# Brushless_Slave2.net
KiCad netlist of a schematic drawn in EAGLE
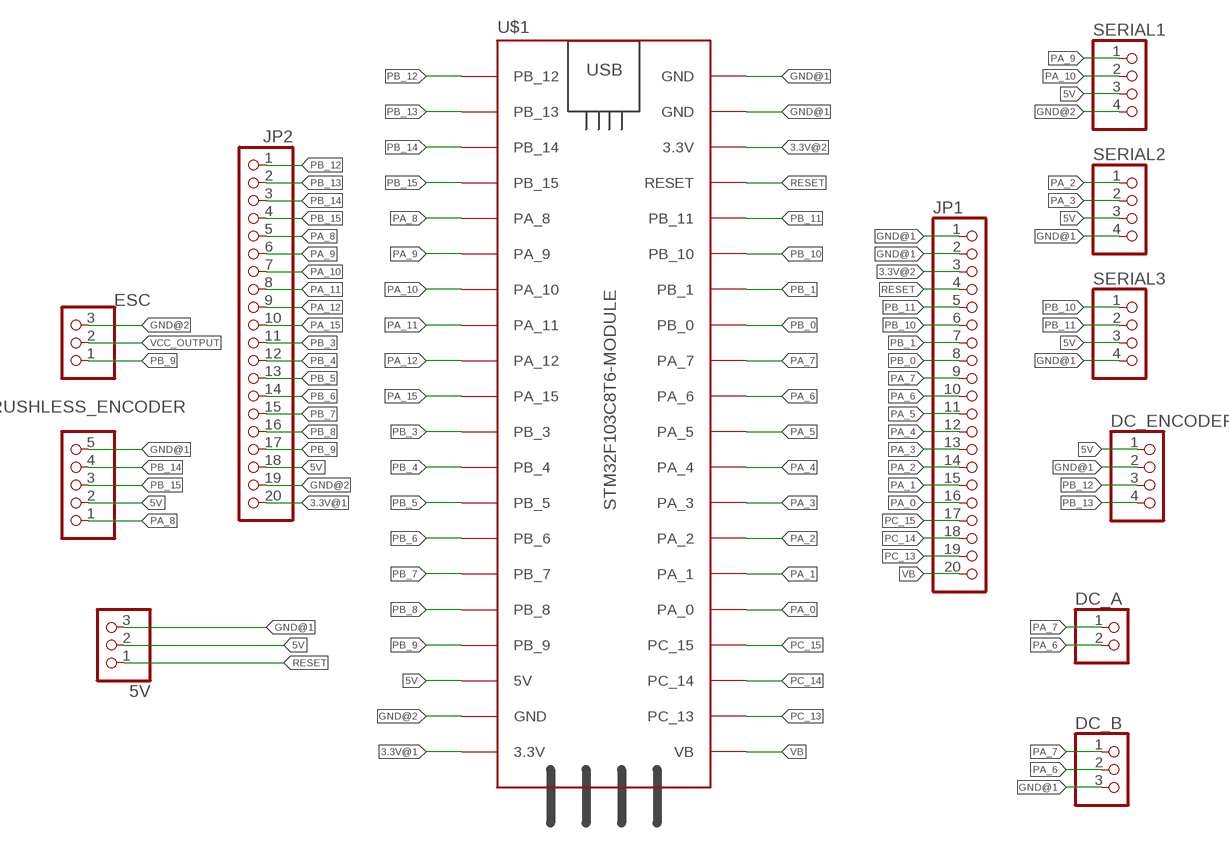
[diagram p0: schematic, sheet 1]

(export (version "E")
  (design (tool "Eeschema 10.0.6"))
  (components
    (comp (ref "5V")
      (value "PINHD-3_DATA")
      (footprint "eagle-import:1X03_DATA")
      (libsource (lib "eagle-import") (part "PINHD-3_DATA"))
    )
    (comp (ref "BRUSHLESS_ENCODER")
      (value "PINHD-5_DATA")
      (footprint "eagle-import:1X05_DATA")
      (libsource (lib "eagle-import") (part "PINHD-5_DATA"))
    )
    (comp (ref "DC_A")
      (value "PINHD-2_DATA")
      (footprint "eagle-import:1X02_DATA")
      (libsource (lib "eagle-import") (part "PINHD-2_DATA"))
    )
    (comp (ref "DC_B")
      (value "PINHD-3_DATA")
      (footprint "eagle-import:1X03_DATA")
      (libsource (lib "eagle-import") (part "PINHD-3_DATA"))
    )
    (comp (ref "DC_ENCODER")
      (value "PINHD-4_DATA")
      (footprint "eagle-import:1X04_DATA")
      (libsource (lib "eagle-import") (part "PINHD-4_DATA"))
    )
    (comp (ref "ESC")
      (value "PINHD-3_DATA")
      (footprint "eagle-import:1X03_DATA")
      (libsource (lib "eagle-import") (part "PINHD-3_DATA"))
    )
    (comp (ref "JP1")
      (value "PINHD-1X20")
      (footprint "eagle-import:1X20")
      (libsource (lib "eagle-import") (part "PINHD-1X20"))
    )
    (comp (ref "JP2")
      (value "PINHD-1X20")
      (footprint "eagle-import:1X20")
      (libsource (lib "eagle-import") (part "PINHD-1X20"))
    )
    (comp (ref "SERIAL1")
      (value "PINHD-4_DATA")
      (footprint "eagle-import:1X04_DATA")
      (libsource (lib "eagle-import") (part "PINHD-4_DATA"))
    )
    (comp (ref "SERIAL2")
      (value "PINHD-4_DATA")
      (footprint "eagle-import:1X04_DATA")
      (libsource (lib "eagle-import") (part "PINHD-4_DATA"))
    )
    (comp (ref "SERIAL3")
      (value "PINHD-4_DATA")
      (footprint "eagle-import:1X04_DATA")
      (libsource (lib "eagle-import") (part "PINHD-4_DATA"))
    )
    (comp (ref "U$1")
      (value "STM32F103C8T6-MODULE")
      (footprint "eagle-import:STM32F103C8T6-MODULE")
      (libsource (lib "eagle-import") (part "STM32F103C8T6-MODULE"))
    )
  )
  (nets
    (net (code "1") (name "3.3V@1") (class "Default")
      (node (ref "JP2") (pin "20") (pinfunction "20_20") (pintype "passive"))
      (node (ref "U$1") (pin "3.3V_1") (pinfunction "3.3V_3.3V_1") (pintype "bidirectional"))
    )
    (net (code "2") (name "3.3V@2") (class "Default")
      (node (ref "JP1") (pin "3") (pinfunction "3_3") (pintype "passive"))
      (node (ref "U$1") (pin "3.3V_2") (pinfunction "3.3V_3.3V_2") (pintype "bidirectional"))
    )
    (net (code "3") (name "5V") (class "Default")
      (node (ref "5V") (pin "2") (pinfunction "2_2") (pintype "passive"))
      (node (ref "BRUSHLESS_ENCODER") (pin "2") (pinfunction "2_2") (pintype "passive"))
      (node (ref "DC_ENCODER") (pin "1") (pinfunction "1_1") (pintype "passive"))
      (node (ref "JP2") (pin "18") (pinfunction "18_18") (pintype "passive"))
      (node (ref "SERIAL1") (pin "3") (pinfunction "3_3") (pintype "passive"))
      (node (ref "SERIAL2") (pin "3") (pinfunction "3_3") (pintype "passive"))
      (node (ref "SERIAL3") (pin "3") (pinfunction "3_3") (pintype "passive"))
      (node (ref "U$1") (pin "5V") (pinfunction "5V_5V") (pintype "bidirectional"))
    )
    (net (code "4") (name "GND@1") (class "Default")
      (node (ref "5V") (pin "3") (pinfunction "3_3") (pintype "passive"))
      (node (ref "BRUSHLESS_ENCODER") (pin "5") (pinfunction "5_5") (pintype "passive"))
      (node (ref "DC_B") (pin "3") (pinfunction "3_3") (pintype "passive"))
      (node (ref "DC_ENCODER") (pin "2") (pinfunction "2_2") (pintype "passive"))
      (node (ref "JP1") (pin "1") (pinfunction "1_1") (pintype "passive"))
      (node (ref "JP1") (pin "2") (pinfunction "2_2") (pintype "passive"))
      (node (ref "SERIAL2") (pin "4") (pinfunction "4_4") (pintype "passive"))
      (node (ref "SERIAL3") (pin "4") (pinfunction "4_4") (pintype "passive"))
      (node (ref "U$1") (pin "GND_2") (pinfunction "GND_GND_2") (pintype "bidirectional"))
      (node (ref "U$1") (pin "GND_3") (pinfunction "GND_GND_3") (pintype "power_in"))
    )
    (net (code "5") (name "GND@2") (class "Default")
      (node (ref "ESC") (pin "3") (pinfunction "3_3") (pintype "passive"))
      (node (ref "JP2") (pin "19") (pinfunction "19_19") (pintype "passive"))
      (node (ref "SERIAL1") (pin "4") (pinfunction "4_4") (pintype "passive"))
      (node (ref "U$1") (pin "GND_1") (pinfunction "GND_GND_1") (pintype "bidirectional"))
    )
    (net (code "6") (name "PA_0") (class "Default")
      (node (ref "JP1") (pin "16") (pinfunction "16_16") (pintype "passive"))
      (node (ref "U$1") (pin "PA_0") (pinfunction "PA_0_PA_0") (pintype "bidirectional"))
    )
    (net (code "7") (name "PA_1") (class "Default")
      (node (ref "JP1") (pin "15") (pinfunction "15_15") (pintype "passive"))
      (node (ref "U$1") (pin "PA_1") (pinfunction "PA_1_PA_1") (pintype "bidirectional"))
    )
    (net (code "8") (name "PA_2") (class "Default")
      (node (ref "JP1") (pin "14") (pinfunction "14_14") (pintype "passive"))
      (node (ref "SERIAL2") (pin "1") (pinfunction "1_1") (pintype "passive"))
      (node (ref "U$1") (pin "PA_2") (pinfunction "PA_2_PA_2") (pintype "bidirectional"))
    )
    (net (code "9") (name "PA_3") (class "Default")
      (node (ref "JP1") (pin "13") (pinfunction "13_13") (pintype "passive"))
      (node (ref "SERIAL2") (pin "2") (pinfunction "2_2") (pintype "passive"))
      (node (ref "U$1") (pin "PA_3") (pinfunction "PA_3_PA_3") (pintype "bidirectional"))
    )
    (net (code "10") (name "PA_4") (class "Default")
      (node (ref "JP1") (pin "12") (pinfunction "12_12") (pintype "passive"))
      (node (ref "U$1") (pin "PA_4") (pinfunction "PA_4_PA_4") (pintype "bidirectional"))
    )
    (net (code "11") (name "PA_5") (class "Default")
      (node (ref "JP1") (pin "11") (pinfunction "11_11") (pintype "passive"))
      (node (ref "U$1") (pin "PA_5") (pinfunction "PA_5_PA_5") (pintype "bidirectional"))
    )
    (net (code "12") (name "PA_6") (class "Default")
      (node (ref "DC_A") (pin "2") (pinfunction "2_2") (pintype "passive"))
      (node (ref "DC_B") (pin "2") (pinfunction "2_2") (pintype "passive"))
      (node (ref "JP1") (pin "10") (pinfunction "10_10") (pintype "passive"))
      (node (ref "U$1") (pin "PA_6") (pinfunction "PA_6_PA_6") (pintype "bidirectional"))
    )
    (net (code "13") (name "PA_7") (class "Default")
      (node (ref "DC_A") (pin "1") (pinfunction "1_1") (pintype "passive"))
      (node (ref "DC_B") (pin "1") (pinfunction "1_1") (pintype "passive"))
      (node (ref "JP1") (pin "9") (pinfunction "9_9") (pintype "passive"))
      (node (ref "U$1") (pin "PA_7") (pinfunction "PA_7_PA_7") (pintype "bidirectional"))
    )
    (net (code "14") (name "PA_8") (class "Default")
      (node (ref "BRUSHLESS_ENCODER") (pin "1") (pinfunction "1_1") (pintype "passive"))
      (node (ref "JP2") (pin "5") (pinfunction "5_5") (pintype "passive"))
      (node (ref "U$1") (pin "PA_8") (pinfunction "PA_8_PA_8") (pintype "bidirectional"))
    )
    (net (code "15") (name "PA_9") (class "Default")
      (node (ref "JP2") (pin "6") (pinfunction "6_6") (pintype "passive"))
      (node (ref "SERIAL1") (pin "1") (pinfunction "1_1") (pintype "passive"))
      (node (ref "U$1") (pin "PA_9") (pinfunction "PA_9_PA_9") (pintype "bidirectional"))
    )
    (net (code "16") (name "PA_10") (class "Default")
      (node (ref "JP2") (pin "7") (pinfunction "7_7") (pintype "passive"))
      (node (ref "SERIAL1") (pin "2") (pinfunction "2_2") (pintype "passive"))
      (node (ref "U$1") (pin "PA_10") (pinfunction "PA_10_PA_10") (pintype "bidirectional"))
    )
    (net (code "17") (name "PA_11") (class "Default")
      (node (ref "JP2") (pin "8") (pinfunction "8_8") (pintype "passive"))
      (node (ref "U$1") (pin "PA_11") (pinfunction "PA_11_PA_11") (pintype "bidirectional"))
    )
    (net (code "18") (name "PA_12") (class "Default")
      (node (ref "JP2") (pin "9") (pinfunction "9_9") (pintype "passive"))
      (node (ref "U$1") (pin "PA_12") (pinfunction "PA_12_PA_12") (pintype "bidirectional"))
    )
    (net (code "19") (name "PA_15") (class "Default")
      (node (ref "JP2") (pin "10") (pinfunction "10_10") (pintype "passive"))
      (node (ref "U$1") (pin "PA_15") (pinfunction "PA_15_PA_15") (pintype "bidirectional"))
    )
    (net (code "20") (name "PB_0") (class "Default")
      (node (ref "JP1") (pin "8") (pinfunction "8_8") (pintype "passive"))
      (node (ref "U$1") (pin "PB_0") (pinfunction "PB_0_PB_0") (pintype "bidirectional"))
    )
    (net (code "21") (name "PB_1") (class "Default")
      (node (ref "JP1") (pin "7") (pinfunction "7_7") (pintype "passive"))
      (node (ref "U$1") (pin "PB_1") (pinfunction "PB_1_PB_1") (pintype "bidirectional"))
    )
    (net (code "22") (name "PB_3") (class "Default")
      (node (ref "JP2") (pin "11") (pinfunction "11_11") (pintype "passive"))
      (node (ref "U$1") (pin "PB_3") (pinfunction "PB_3_PB_3") (pintype "bidirectional"))
    )
    (net (code "23") (name "PB_4") (class "Default")
      (node (ref "JP2") (pin "12") (pinfunction "12_12") (pintype "passive"))
      (node (ref "U$1") (pin "PB_4") (pinfunction "PB_4_PB_4") (pintype "bidirectional"))
    )
    (net (code "24") (name "PB_5") (class "Default")
      (node (ref "JP2") (pin "13") (pinfunction "13_13") (pintype "passive"))
      (node (ref "U$1") (pin "PB_5") (pinfunction "PB_5_PB_5") (pintype "bidirectional"))
    )
    (net (code "25") (name "PB_6") (class "Default")
      (node (ref "JP2") (pin "14") (pinfunction "14_14") (pintype "passive"))
      (node (ref "U$1") (pin "PB_6") (pinfunction "PB_6_PB_6") (pintype "bidirectional"))
    )
    (net (code "26") (name "PB_7") (class "Default")
      (node (ref "JP2") (pin "15") (pinfunction "15_15") (pintype "passive"))
      (node (ref "U$1") (pin "PB_7") (pinfunction "PB_7_PB_7") (pintype "bidirectional"))
    )
    (net (code "27") (name "PB_8") (class "Default")
      (node (ref "JP2") (pin "16") (pinfunction "16_16") (pintype "passive"))
      (node (ref "U$1") (pin "PB_8") (pinfunction "PB_8_PB_8") (pintype "bidirectional"))
    )
    (net (code "28") (name "PB_9") (class "Default")
      (node (ref "ESC") (pin "1") (pinfunction "1_1") (pintype "passive"))
      (node (ref "JP2") (pin "17") (pinfunction "17_17") (pintype "passive"))
      (node (ref "U$1") (pin "PB_9") (pinfunction "PB_9_PB_9") (pintype "bidirectional"))
    )
    (net (code "29") (name "PB_10") (class "Default")
      (node (ref "JP1") (pin "6") (pinfunction "6_6") (pintype "passive"))
      (node (ref "SERIAL3") (pin "1") (pinfunction "1_1") (pintype "passive"))
      (node (ref "U$1") (pin "PB_10") (pinfunction "PB_10_PB_10") (pintype "bidirectional"))
    )
    (net (code "30") (name "PB_11") (class "Default")
      (node (ref "JP1") (pin "5") (pinfunction "5_5") (pintype "passive"))
      (node (ref "SERIAL3") (pin "2") (pinfunction "2_2") (pintype "passive"))
      (node (ref "U$1") (pin "PB_11") (pinfunction "PB_11_PB_11") (pintype "bidirectional"))
    )
    (net (code "31") (name "PB_12") (class "Default")
      (node (ref "DC_ENCODER") (pin "3") (pinfunction "3_3") (pintype "passive"))
      (node (ref "JP2") (pin "1") (pinfunction "1_1") (pintype "passive"))
      (node (ref "U$1") (pin "PB_12") (pinfunction "PB_12_PB_12") (pintype "bidirectional"))
    )
    (net (code "32") (name "PB_13") (class "Default")
      (node (ref "DC_ENCODER") (pin "4") (pinfunction "4_4") (pintype "passive"))
      (node (ref "JP2") (pin "2") (pinfunction "2_2") (pintype "passive"))
      (node (ref "U$1") (pin "PB_13") (pinfunction "PB_13_PB_13") (pintype "bidirectional"))
    )
    (net (code "33") (name "PB_14") (class "Default")
      (node (ref "BRUSHLESS_ENCODER") (pin "4") (pinfunction "4_4") (pintype "passive"))
      (node (ref "JP2") (pin "3") (pinfunction "3_3") (pintype "passive"))
      (node (ref "U$1") (pin "PB_14") (pinfunction "PB_14_PB_14") (pintype "bidirectional"))
    )
    (net (code "34") (name "PB_15") (class "Default")
      (node (ref "BRUSHLESS_ENCODER") (pin "3") (pinfunction "3_3") (pintype "passive"))
      (node (ref "JP2") (pin "4") (pinfunction "4_4") (pintype "passive"))
      (node (ref "U$1") (pin "PB_15") (pinfunction "PB_15_PB_15") (pintype "bidirectional"))
    )
    (net (code "35") (name "PC_13") (class "Default")
      (node (ref "JP1") (pin "19") (pinfunction "19_19") (pintype "passive"))
      (node (ref "U$1") (pin "PC_13") (pinfunction "PC_13_PC_13") (pintype "bidirectional"))
    )
    (net (code "36") (name "PC_14") (class "Default")
      (node (ref "JP1") (pin "18") (pinfunction "18_18") (pintype "passive"))
      (node (ref "U$1") (pin "PC_14") (pinfunction "PC_14_PC_14") (pintype "bidirectional"))
    )
    (net (code "37") (name "PC_15") (class "Default")
      (node (ref "JP1") (pin "17") (pinfunction "17_17") (pintype "passive"))
      (node (ref "U$1") (pin "PC_15") (pinfunction "PC_15_PC_15") (pintype "bidirectional"))
    )
    (net (code "38") (name "RESET") (class "Default")
      (node (ref "5V") (pin "1") (pinfunction "1_1") (pintype "passive"))
      (node (ref "JP1") (pin "4") (pinfunction "4_4") (pintype "passive"))
      (node (ref "U$1") (pin "RESET") (pinfunction "RESET_RESET") (pintype "bidirectional"))
    )
    (net (code "39") (name "VB") (class "Default")
      (node (ref "JP1") (pin "20") (pinfunction "20_20") (pintype "passive"))
      (node (ref "U$1") (pin "VB") (pinfunction "VB_VB") (pintype "bidirectional"))
    )
    (net (code "40") (name "VCC_OUTPUT") (class "Default")
      (node (ref "ESC") (pin "2") (pinfunction "2_2") (pintype "passive"))
    )
  )
)
